# project-schematic.net
KiCad netlist of a schematic drawn in Altium Designer
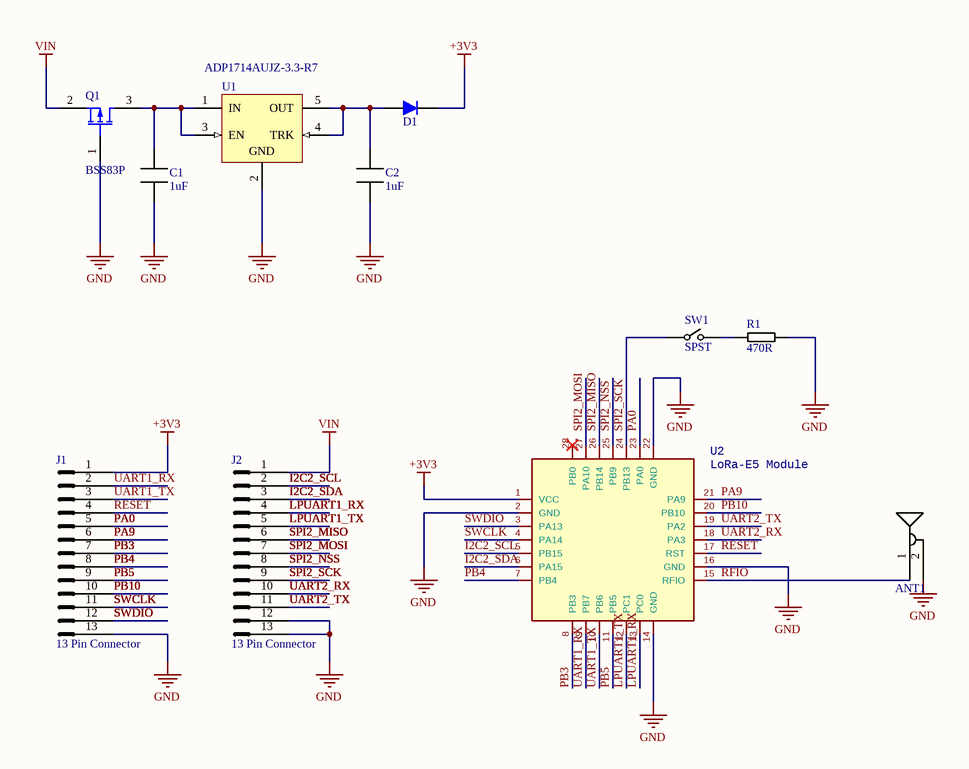
[diagram p0: project-schematic.SchDoc]

(export (version "E")
  (design (tool "Eeschema 10.0.6"))
  (components
    (comp (ref "ANT1")
      (value "Antenna")
      (footprint "Linx-ANT-915-uSP410")
      (description "915 MHz Antenna")
      (libsource (lib "project-schematic-library") (part "915 MHz Antenna"))
    )
    (comp (ref "C1")
      (value "1uF")
      (footprint "CAPACITOR_0603")
      (description "Generic Capacitor")
      (libsource (lib "project-schematic-library") (part "Capacitor"))
    )
    (comp (ref "C2")
      (value "1uF")
      (footprint "CAPACITOR_0603")
      (description "Generic Capacitor")
      (libsource (lib "project-schematic-library") (part "Capacitor"))
    )
    (comp (ref "D1")
      (value "Schottky Diode")
      (footprint "SODFL350X90-2N")
      (description "Schottky Barrier Diode")
      (libsource (lib "project-schematic-library") (part "Diode"))
    )
    (comp (ref "J1")
      (value "13 Pin Connector")
      (footprint "Connector-Pin-Header-2.54mm-1x13 - duplicate")
      (libsource (lib "project-schematic-library") (part "Connector-Male-1x13"))
    )
    (comp (ref "J2")
      (value "13 Pin Connector")
      (footprint "Connector-Pin-Header-2.54mm-1x13 - duplicate")
      (libsource (lib "project-schematic-library") (part "Connector-Male-1x13"))
    )
    (comp (ref "Q1")
      (value "BSS83P")
      (footprint "INF-PG-SOT23_N")
      (fields (field (name "MANUFACTURER") "Infineon"))
      (libsource (lib "Altium Content Vault") (part "INF-BSS83P-PG-SOT23-3"))
    )
    (comp (ref "R1")
      (value "470R")
      (footprint "Resistor_0603")
      (description "Generic 0603 Resistor")
      (libsource (lib "project-schematic-library") (part "Resistor"))
    )
    (comp (ref "SW1")
      (value "SPST")
      (footprint "TL3342")
      (description "Single Pole Single Throw Switch")
      (libsource (lib "project-schematic-library") (part "SPST Switch"))
    )
    (comp (ref "U1")
      (value "ADP1714AUJZ-3.3-R7")
      (footprint "ADI-UJ-5_M")
      (fields (field (name "MANUFACTURER") "Analog Devices"))
      (libsource (lib "Altium Content Vault") (part "ADI-ADP1714-UJ-5"))
    )
    (comp (ref "U2")
      (value "LoRa-E5 Module")
      (footprint "LoRa-e5")
      (description "ARM Cortex-M4 and SX126x embedded, supports LoRaWAN on EU868 & US915")
      (libsource (lib "project-schematic-library") (part "LoRa-E5"))
    )
  )
  (nets
    (net (code "1") (name "+3V3") (class "Default")
      (node (ref "D1") (pin "2") (pintype "passive"))
      (node (ref "J1") (pin "1") (pinfunction "-_1") (pintype "passive"))
      (node (ref "U2") (pin "1") (pinfunction "VCC_1") (pintype "passive"))
    )
    (net (code "2") (name "/I2C2_SCL") (class "Default")
      (node (ref "J2") (pin "2") (pinfunction "-_2") (pintype "passive"))
      (node (ref "U2") (pin "5") (pinfunction "PB15_5") (pintype "passive"))
    )
    (net (code "3") (name "/I2C2_SDA") (class "Default")
      (node (ref "J2") (pin "3") (pinfunction "-_3") (pintype "passive"))
      (node (ref "U2") (pin "6") (pinfunction "PA15_6") (pintype "passive"))
    )
    (net (code "4") (name "/LPUART1_RX") (class "Default")
      (node (ref "J2") (pin "4") (pinfunction "-_4") (pintype "passive"))
      (node (ref "U2") (pin "13") (pinfunction "PC0_13") (pintype "passive"))
    )
    (net (code "5") (name "/LPUART1_TX") (class "Default")
      (node (ref "J2") (pin "5") (pinfunction "-_5") (pintype "passive"))
      (node (ref "U2") (pin "12") (pinfunction "PC1_12") (pintype "passive"))
    )
    (net (code "6") (name "/PA0") (class "Default")
      (node (ref "J1") (pin "5") (pinfunction "-_5") (pintype "passive"))
      (node (ref "U2") (pin "23") (pinfunction "PA0_23") (pintype "passive"))
    )
    (net (code "7") (name "/PA9") (class "Default")
      (node (ref "J1") (pin "6") (pinfunction "-_6") (pintype "passive"))
      (node (ref "U2") (pin "21") (pinfunction "PA9_21") (pintype "passive"))
    )
    (net (code "8") (name "/PB3") (class "Default")
      (node (ref "J1") (pin "7") (pinfunction "-_7") (pintype "passive"))
      (node (ref "U2") (pin "8") (pinfunction "PB3_8") (pintype "passive"))
    )
    (net (code "9") (name "/PB4") (class "Default")
      (node (ref "J1") (pin "8") (pinfunction "-_8") (pintype "passive"))
      (node (ref "U2") (pin "7") (pinfunction "PB4_7") (pintype "passive"))
    )
    (net (code "10") (name "/PB5") (class "Default")
      (node (ref "J1") (pin "9") (pinfunction "-_9") (pintype "passive"))
      (node (ref "U2") (pin "11") (pinfunction "PB5_11") (pintype "passive"))
    )
    (net (code "11") (name "/PB10") (class "Default")
      (node (ref "J1") (pin "10") (pinfunction "-_10") (pintype "passive"))
      (node (ref "U2") (pin "20") (pinfunction "PB10_20") (pintype "passive"))
    )
    (net (code "12") (name "/RESET") (class "Default")
      (node (ref "J1") (pin "4") (pinfunction "-_4") (pintype "passive"))
      (node (ref "U2") (pin "17") (pinfunction "RST_17") (pintype "passive"))
    )
    (net (code "13") (name "/RFIO") (class "Default")
      (node (ref "ANT1") (pin "1") (pinfunction "-_1") (pintype "passive"))
      (node (ref "U2") (pin "15") (pinfunction "RFIO_15") (pintype "passive"))
    )
    (net (code "14") (name "/SPI2_MISO") (class "Default")
      (node (ref "J2") (pin "6") (pinfunction "-_6") (pintype "passive"))
      (node (ref "U2") (pin "26") (pinfunction "PB14_26") (pintype "passive"))
    )
    (net (code "15") (name "/SPI2_MOSI") (class "Default")
      (node (ref "J2") (pin "7") (pinfunction "-_7") (pintype "passive"))
      (node (ref "U2") (pin "27") (pinfunction "PA10_27") (pintype "passive"))
    )
    (net (code "16") (name "/SPI2_NSS") (class "Default")
      (node (ref "J2") (pin "8") (pinfunction "-_8") (pintype "passive"))
      (node (ref "U2") (pin "25") (pinfunction "PB9_25") (pintype "passive"))
    )
    (net (code "17") (name "/SPI2_SCK") (class "Default")
      (node (ref "J2") (pin "9") (pinfunction "-_9") (pintype "passive"))
      (node (ref "SW1") (pin "1") (pinfunction "-_1") (pintype "passive"))
      (node (ref "U2") (pin "24") (pinfunction "PB13_24") (pintype "passive"))
    )
    (net (code "18") (name "/SWCLK") (class "Default")
      (node (ref "J1") (pin "11") (pinfunction "-_11") (pintype "passive"))
      (node (ref "U2") (pin "4") (pinfunction "PA14_4") (pintype "passive"))
    )
    (net (code "19") (name "/SWDIO") (class "Default")
      (node (ref "J1") (pin "12") (pinfunction "-_12") (pintype "passive"))
      (node (ref "U2") (pin "3") (pinfunction "PA13_3") (pintype "passive"))
    )
    (net (code "20") (name "/UART1_RX") (class "Default")
      (node (ref "J1") (pin "2") (pinfunction "-_2") (pintype "passive"))
      (node (ref "U2") (pin "9") (pinfunction "PB7_9") (pintype "passive"))
    )
    (net (code "21") (name "/UART1_TX") (class "Default")
      (node (ref "J1") (pin "3") (pinfunction "-_3") (pintype "passive"))
      (node (ref "U2") (pin "10") (pinfunction "PB6_10") (pintype "passive"))
    )
    (net (code "22") (name "/UART2_RX") (class "Default")
      (node (ref "J2") (pin "10") (pinfunction "-_10") (pintype "passive"))
      (node (ref "U2") (pin "18") (pinfunction "PA3_18") (pintype "passive"))
    )
    (net (code "23") (name "/UART2_TX") (class "Default")
      (node (ref "J2") (pin "11") (pinfunction "-_11") (pintype "passive"))
      (node (ref "U2") (pin "19") (pinfunction "PA2_19") (pintype "passive"))
    )
    (net (code "24") (name "GND") (class "Default")
      (node (ref "ANT1") (pin "2") (pinfunction "-_2") (pintype "passive"))
      (node (ref "C1") (pin "1") (pintype "passive"))
      (node (ref "C2") (pin "1") (pintype "passive"))
      (node (ref "J1") (pin "13") (pinfunction "-_13") (pintype "passive"))
      (node (ref "J2") (pin "12") (pinfunction "-_12") (pintype "passive"))
      (node (ref "J2") (pin "13") (pinfunction "-_13") (pintype "passive"))
      (node (ref "Q1") (pin "1") (pinfunction "G_1") (pintype "passive"))
      (node (ref "R1") (pin "2") (pintype "passive"))
      (node (ref "U1") (pin "2") (pinfunction "GND_2") (pintype "power_in"))
      (node (ref "U2") (pin "14") (pinfunction "GND_14") (pintype "passive"))
      (node (ref "U2") (pin "16") (pinfunction "GND_16") (pintype "passive"))
      (node (ref "U2") (pin "2") (pinfunction "GND_2") (pintype "passive"))
      (node (ref "U2") (pin "22") (pinfunction "GND_22") (pintype "passive"))
    )
    (net (code "25") (name "Net-(Q1-D)") (class "Default")
      (node (ref "C1") (pin "2") (pintype "passive"))
      (node (ref "Q1") (pin "3") (pinfunction "D_3") (pintype "passive"))
      (node (ref "U1") (pin "1") (pinfunction "IN_1") (pintype "power_in"))
      (node (ref "U1") (pin "3") (pinfunction "EN_3") (pintype "input"))
    )
    (net (code "26") (name "Net-(R1-Pad1)") (class "Default")
      (node (ref "R1") (pin "1") (pintype "passive"))
      (node (ref "SW1") (pin "2") (pinfunction "2_2") (pintype "passive"))
    )
    (net (code "27") (name "Net-(U1-OUT)") (class "Default")
      (node (ref "C2") (pin "2") (pintype "passive"))
      (node (ref "D1") (pin "1") (pintype "passive"))
      (node (ref "U1") (pin "4") (pinfunction "TRK_4") (pintype "input"))
      (node (ref "U1") (pin "5") (pinfunction "OUT_5") (pintype "power_in"))
    )
    (net (code "28") (name "VIN") (class "Default")
      (node (ref "J2") (pin "1") (pinfunction "-_1") (pintype "passive"))
      (node (ref "Q1") (pin "2") (pinfunction "S_2") (pintype "passive"))
    )
    (net (code "29") (name "unconnected-(U2-PB0-Pad28)") (class "Default")
      (node (ref "U2") (pin "28") (pinfunction "PB0_28") (pintype "passive+no_connect"))
    )
  )
)
